# TXPA-24dB.net
KiCad netlist of a schematic drawn in Altium Designer
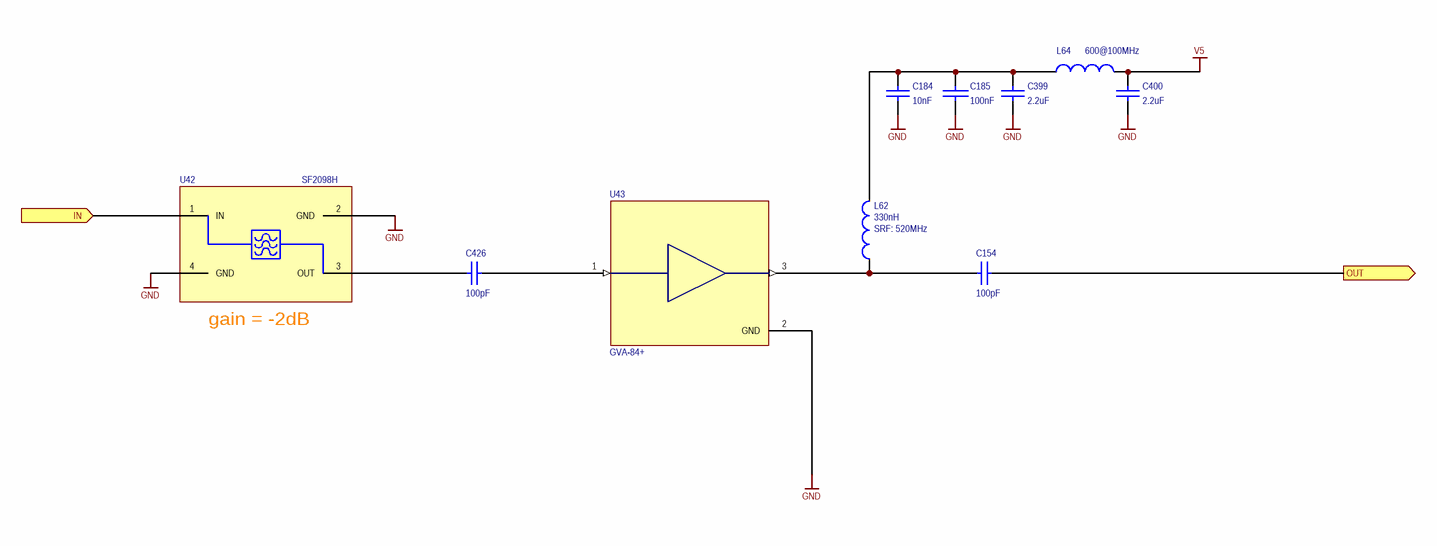
[diagram p0: TXPA-24dB.SchDoc]

(export (version "E")
  (design (tool "Eeschema 10.0.6"))
  (components
    (comp (ref "C154")
      (value "100pF")
      (footprint "0402")
      (description "Ceramic Capacitor 100pF ±1% 25V NP0 0402")
      (fields (field (name "VOLTAGE") "25V") (field (name "MANUFACTURER") "Kemet"))
      (libsource (lib "generic") (part "CAP 0603"))
    )
    (comp (ref "C184")
      (value "10nF")
      (footprint "generic:0402")
      (description "Ceramic Capacitor 10nF ±10% 25V X7R 0402")
      (fields (field (name "VOLTAGE") "25V") (field (name "MANUFACTURER") "Murata"))
      (libsource (lib "Graviton") (part "CAP 0402"))
    )
    (comp (ref "C185")
      (value "100nF")
      (footprint "generic:0402")
      (description "Ceramic Capacitor 100nF ±10% 16V X7R 0402")
      (fields (field (name "MANUFACTURER") "Murata") (field (name "VOLTAGE") "16V"))
      (libsource (lib "*") (part "CAP"))
    )
    (comp (ref "C399")
      (value "2.2uF")
      (footprint "generic:0805")
      (description "Ceramic Capacitor 2.2uF ±10% 10V X7R 0805")
      (fields (field (name "VOLTAGE") "10V") (field (name "MANUFACTURER") "Murata"))
      (libsource (lib "Graviton") (part "CAP 0805"))
    )
    (comp (ref "C400")
      (value "2.2uF")
      (footprint "generic:0805")
      (description "Ceramic Capacitor 2.2uF ±10% 10V X7R 0805")
      (fields (field (name "VOLTAGE") "10V") (field (name "MANUFACTURER") "Murata"))
      (libsource (lib "Graviton") (part "CAP 0805"))
    )
    (comp (ref "C426")
      (value "100pF")
      (footprint "0402")
      (description "Ceramic Capacitor 100pF ±1% 25V NP0 0402")
      (fields (field (name "MANUFACTURER") "Kemet") (field (name "VOLTAGE") "25V"))
      (libsource (lib "generic") (part "CAP 0603"))
    )
    (comp (ref "L62")
      (value "330nH")
      (footprint "INDC1005X55N")
      (description "Wirewound Inductor 330nH 390mA 0402")
      (fields
        (field (name "MANUFACTURER") "Murata")
        (field (name "SRF") "520MHz")
        (field (name "Comment") "LQW15CNR33J10D")
      )
      (libsource (lib "Graviton") (part "IND 0603"))
    )
    (comp (ref "L64")
      (value "600@100MHz")
      (footprint "0402")
      (description "Ferrite Bead 600-Ohm @ 100MHz 900mA 0402")
      (fields (field (name "MANUFACTURER") "Murata") (field (name "TOLERANCE") "±25%"))
      (libsource (lib "Graviton") (part "IND 0402"))
    )
    (comp (ref "U42")
      (value "SF2098H")
      (footprint "rfm:SM2016-4")
      (description "915 MHz SAW Filter")
      (fields (field (name "MANUFACTURER") "RFM"))
      (libsource (lib "rfm") (part "SF2098H"))
    )
    (comp (ref "U43")
      (value "GVA-84+")
      (footprint "SOT89")
      (description "High Gain Monolithic Amplifier, DC-7GHz 24dB Gain")
      (fields (field (name "MANUFACTURER") "Mini-Circuits"))
      (libsource (lib "Mini-Circuits") (part "GVA-84+"))
    )
  )
  (nets
    (net (code "1") (name "/IN") (class "Default")
      (node (ref "U42") (pin "1") (pinfunction "IN_1") (pintype "passive"))
    )
    (net (code "2") (name "/OUT") (class "Default")
      (node (ref "C154") (pin "2") (pinfunction "2_2") (pintype "passive"))
    )
    (net (code "3") (name "GND") (class "Default")
      (node (ref "C184") (pin "1") (pinfunction "1_1") (pintype "passive"))
      (node (ref "C185") (pin "1") (pinfunction "1_1") (pintype "passive"))
      (node (ref "C399") (pin "1") (pinfunction "1_1") (pintype "passive"))
      (node (ref "C400") (pin "1") (pinfunction "1_1") (pintype "passive"))
      (node (ref "U42") (pin "2") (pinfunction "GND_2") (pintype "passive"))
      (node (ref "U42") (pin "4") (pinfunction "GND_4") (pintype "passive"))
      (node (ref "U43") (pin "2") (pinfunction "GND_2") (pintype "passive"))
    )
    (net (code "4") (name "Net-(C184-Pad2)") (class "Default")
      (node (ref "C184") (pin "2") (pinfunction "2_2") (pintype "passive"))
      (node (ref "C185") (pin "2") (pinfunction "2_2") (pintype "passive"))
      (node (ref "C399") (pin "2") (pinfunction "2_2") (pintype "passive"))
      (node (ref "L62") (pin "2") (pinfunction "2_2") (pintype "passive"))
      (node (ref "L64") (pin "2") (pinfunction "2_2") (pintype "passive"))
    )
    (net (code "5") (name "Net-(U42-OUT)") (class "Default")
      (node (ref "C426") (pin "1") (pinfunction "1_1") (pintype "passive"))
      (node (ref "U42") (pin "3") (pinfunction "OUT_3") (pintype "passive"))
    )
    (net (code "6") (name "Net-(U43-RFIN)") (class "Default")
      (node (ref "C426") (pin "2") (pinfunction "2_2") (pintype "passive"))
      (node (ref "U43") (pin "1") (pinfunction "RFIN_1") (pintype "input"))
    )
    (net (code "7") (name "Net-(U43-RFOUT)") (class "Default")
      (node (ref "C154") (pin "1") (pinfunction "1_1") (pintype "passive"))
      (node (ref "L62") (pin "1") (pinfunction "1_1") (pintype "passive"))
      (node (ref "U43") (pin "3") (pinfunction "RFOUT_3") (pintype "output"))
    )
    (net (code "8") (name "V5") (class "Default")
      (node (ref "C400") (pin "2") (pinfunction "2_2") (pintype "passive"))
      (node (ref "L64") (pin "1") (pinfunction "1_1") (pintype "passive"))
    )
  )
)
